# Moodlamp.net
KiCad netlist of a schematic drawn in EAGLE
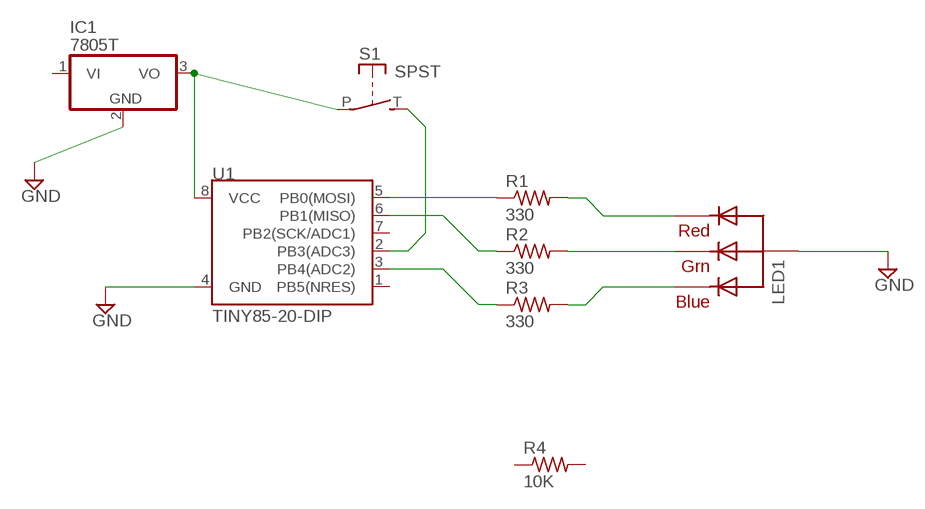
[diagram p0: schematic, sheet 1]

(export (version "E")
  (design (tool "Eeschema 10.0.6"))
  (components
    (comp (ref "IC1")
      (value "7805T")
      (footprint "eagle-import:TO220H")
      (libsource (lib "eagle-import") (part "78T05"))
    )
    (comp (ref "LED1")
      (value "RGBLED_CA-5MM")
      (footprint "eagle-import:LED5MMRGB")
      (libsource (lib "eagle-import") (part "RGBLED_CA-5MM"))
    )
    (comp (ref "R1")
      (value "330")
      (footprint "eagle-import:0207_10")
      (libsource (lib "eagle-import") (part "R-US_0207/10"))
    )
    (comp (ref "R2")
      (value "330")
      (footprint "eagle-import:0207_10")
      (libsource (lib "eagle-import") (part "R-US_0207/10"))
    )
    (comp (ref "R3")
      (value "330")
      (footprint "eagle-import:0207_10")
      (libsource (lib "eagle-import") (part "R-US_0207/10"))
    )
    (comp (ref "R4")
      (value "10K")
      (footprint "eagle-import:0207_10")
      (libsource (lib "eagle-import") (part "R-US_0207/10"))
    )
    (comp (ref "S1")
      (value "SPST")
      (footprint "eagle-import:JUDCOSPST")
      (libsource (lib "eagle-import") (part "SPST"))
    )
    (comp (ref "U1")
      (value "TINY85-20-DIP")
      (footprint "eagle-import:DIP08")
      (libsource (lib "eagle-import") (part "ATTINY45TINY85-20-DIP"))
    )
  )
  (nets
    (net (code "1") (name "GND") (class "Default")
      (node (ref "IC1") (pin "2") (pinfunction "GND_2") (pintype "passive"))
      (node (ref "LED1") (pin "2") (pinfunction "VCC_2") (pintype "bidirectional"))
      (node (ref "U1") (pin "4") (pinfunction "GND_4") (pintype "bidirectional"))
    )
    (net (code "2") (name "Net-(IC1-VO)") (class "Default")
      (node (ref "IC1") (pin "3") (pinfunction "VO_3") (pintype "passive"))
      (node (ref "S1") (pin "P") (pinfunction "P_P") (pintype "passive"))
      (node (ref "U1") (pin "8") (pinfunction "VCC_8") (pintype "bidirectional"))
    )
    (net (code "3") (name "Net-(LED1-BLUE)") (class "Default")
      (node (ref "LED1") (pin "4") (pinfunction "BLUE_4") (pintype "bidirectional"))
      (node (ref "R3") (pin "2") (pinfunction "2_2") (pintype "passive"))
    )
    (net (code "4") (name "Net-(LED1-GREEN)") (class "Default")
      (node (ref "LED1") (pin "3") (pinfunction "GREEN_3") (pintype "bidirectional"))
      (node (ref "R2") (pin "2") (pinfunction "2_2") (pintype "passive"))
    )
    (net (code "5") (name "Net-(LED1-RED)") (class "Default")
      (node (ref "LED1") (pin "1") (pinfunction "RED_1") (pintype "bidirectional"))
      (node (ref "R1") (pin "2") (pinfunction "2_2") (pintype "passive"))
    )
    (net (code "6") (name "Net-(S1-S)") (class "Default")
      (node (ref "S1") (pin "T") (pinfunction "S_T") (pintype "passive"))
      (node (ref "U1") (pin "2") (pinfunction "PB3(ADC3)_2") (pintype "bidirectional"))
    )
    (net (code "7") (name "Net-(U1-PB0(MOSI))") (class "Default")
      (node (ref "R1") (pin "1") (pinfunction "1_1") (pintype "passive"))
      (node (ref "U1") (pin "5") (pinfunction "PB0(MOSI)_5") (pintype "bidirectional"))
    )
    (net (code "8") (name "Net-(U1-PB1(MISO))") (class "Default")
      (node (ref "R2") (pin "1") (pinfunction "1_1") (pintype "passive"))
      (node (ref "U1") (pin "6") (pinfunction "PB1(MISO)_6") (pintype "bidirectional"))
    )
    (net (code "9") (name "Net-(U1-PB4(ADC2))") (class "Default")
      (node (ref "R3") (pin "1") (pinfunction "1_1") (pintype "passive"))
      (node (ref "U1") (pin "3") (pinfunction "PB4(ADC2)_3") (pintype "bidirectional"))
    )
    (net (code "10") (name "unconnected-(IC1-VI-Pad1)") (class "Default")
      (node (ref "IC1") (pin "1") (pinfunction "VI_1") (pintype "input"))
    )
    (net (code "11") (name "unconnected-(R4-Pad1)") (class "Default")
      (node (ref "R4") (pin "1") (pinfunction "1_1") (pintype "passive"))
    )
    (net (code "12") (name "unconnected-(R4-Pad2)") (class "Default")
      (node (ref "R4") (pin "2") (pinfunction "2_2") (pintype "passive"))
    )
    (net (code "13") (name "unconnected-(U1-PB2(SCK{slash}ADC1)-Pad7)") (class "Default")
      (node (ref "U1") (pin "7") (pinfunction "PB2(SCK/ADC1)_7") (pintype "bidirectional"))
    )
    (net (code "14") (name "unconnected-(U1-PB5(NRES)-Pad1)") (class "Default")
      (node (ref "U1") (pin "1") (pinfunction "PB5(NRES)_1") (pintype "bidirectional"))
    )
  )
)
